# Irrigatron.net
KiCad netlist of a schematic drawn in EasyEDA
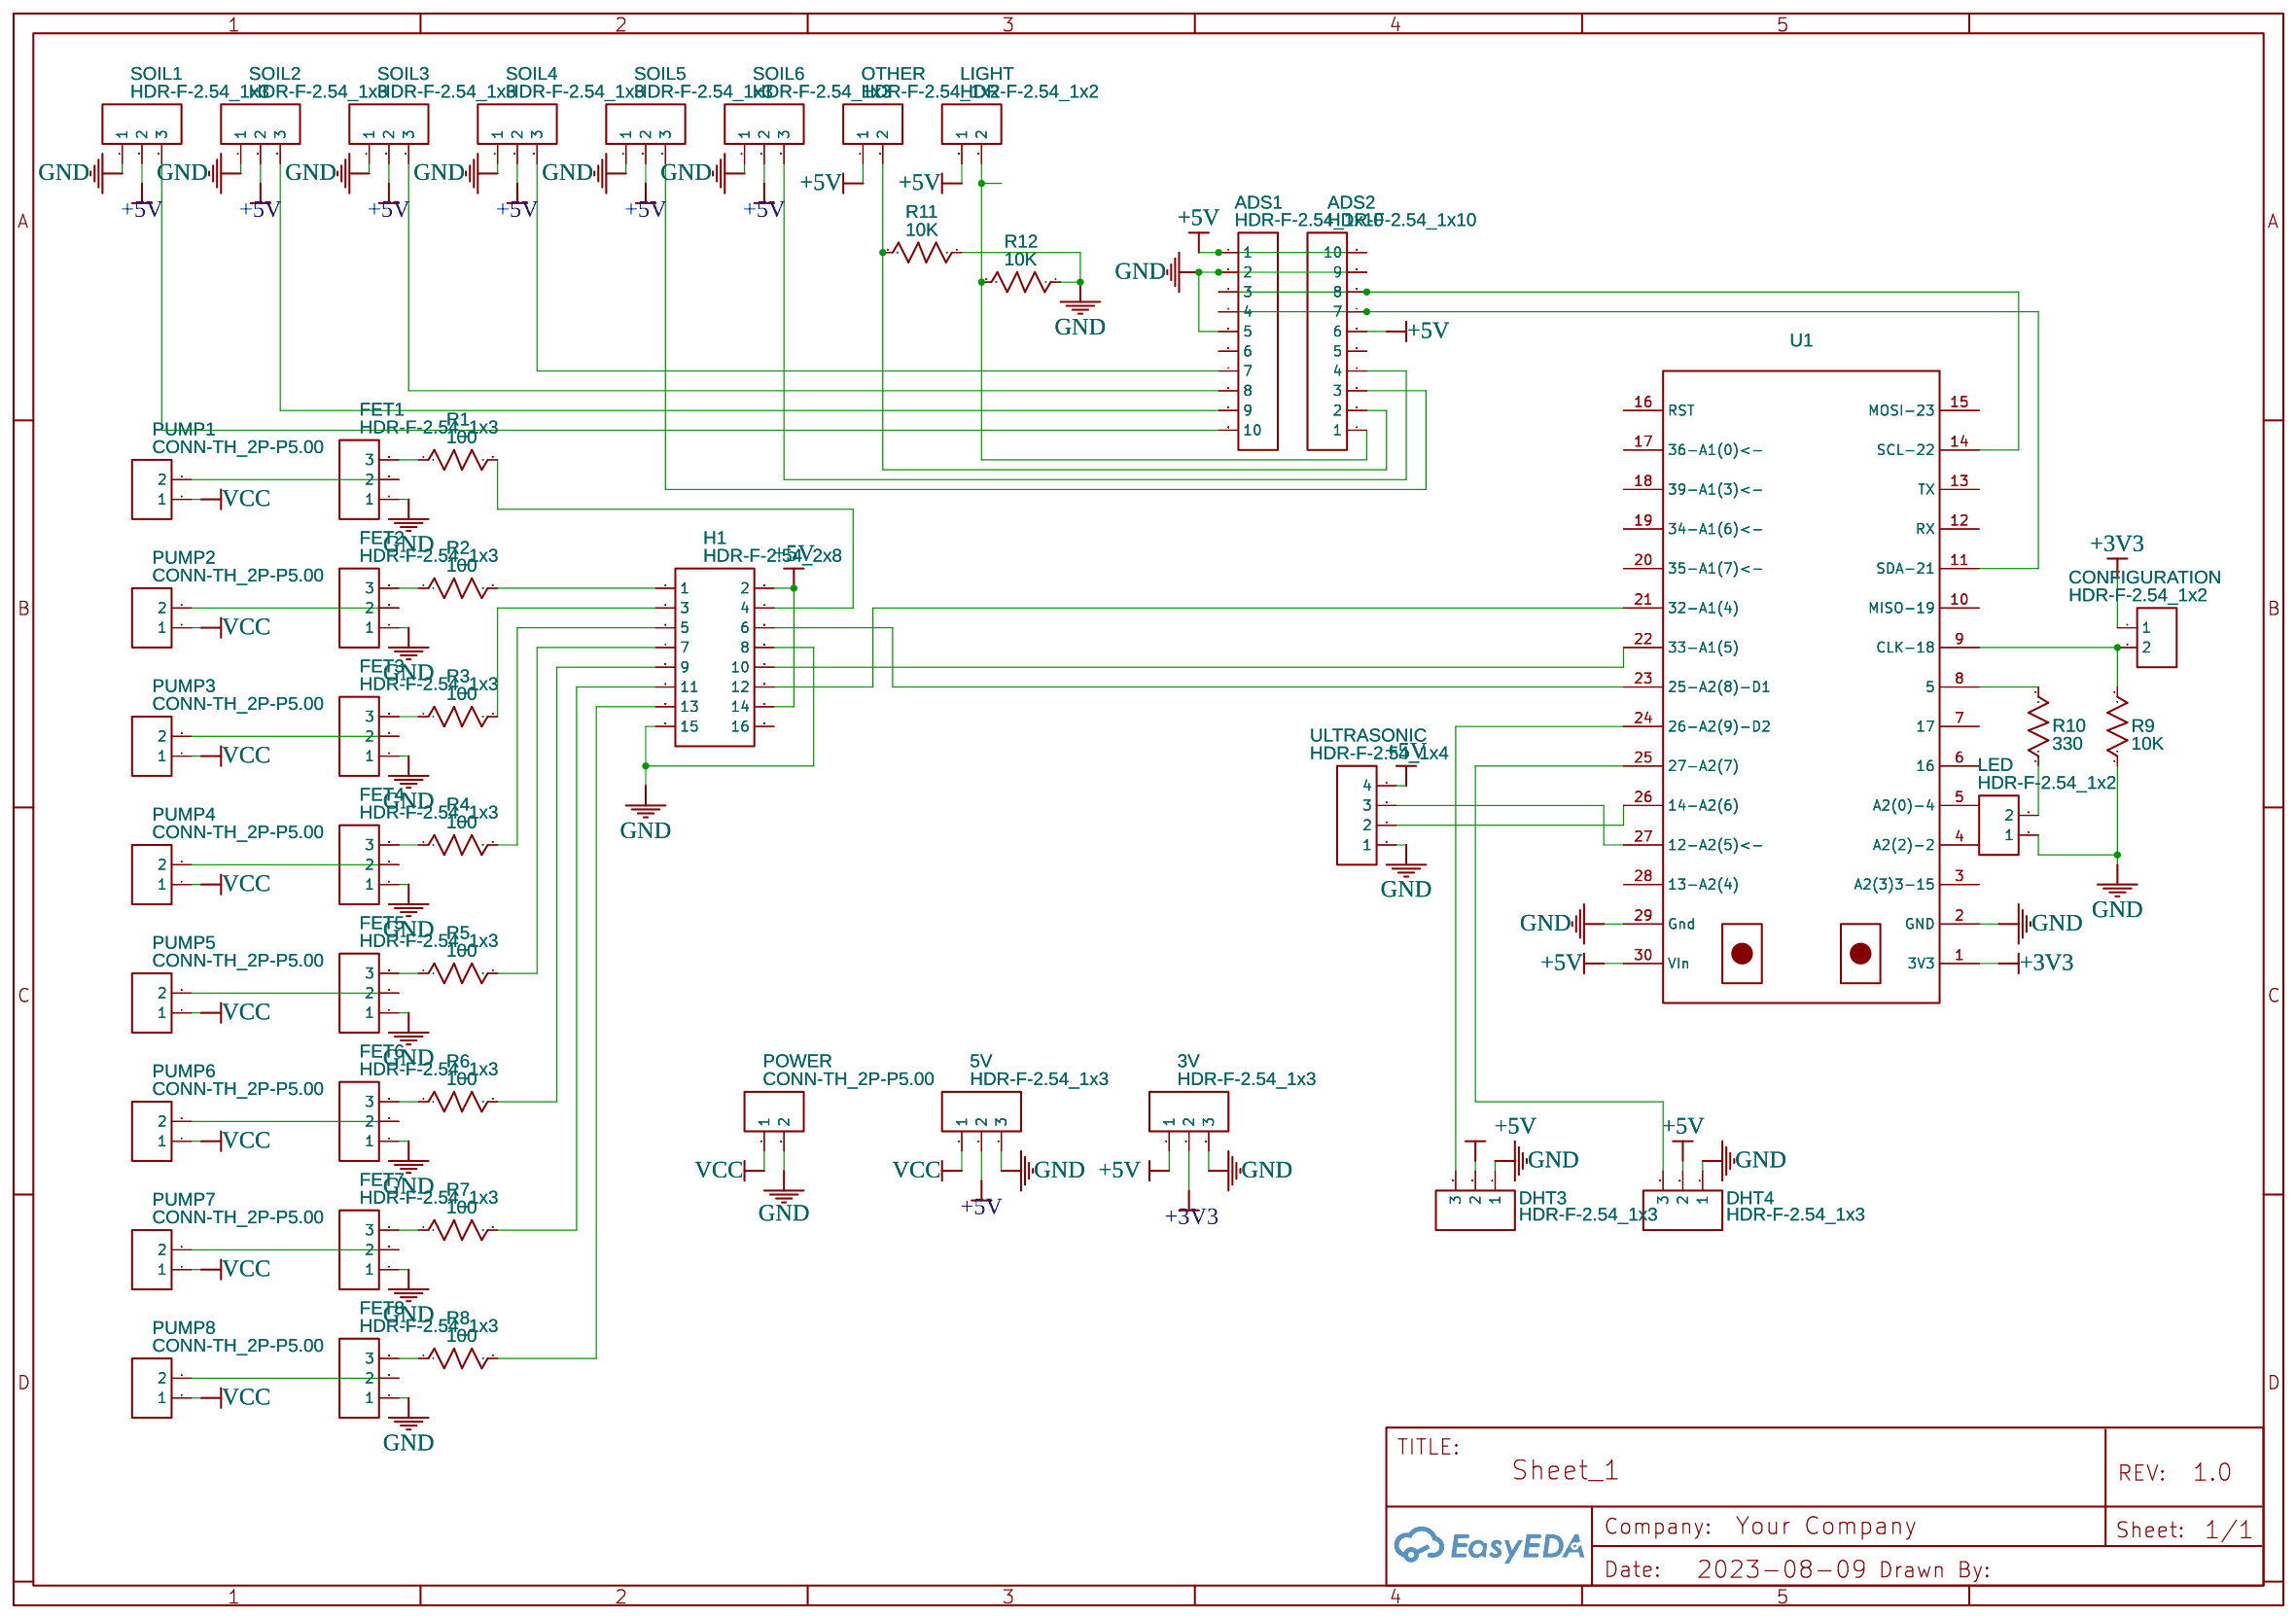
[diagram p0: schematic sheet]

(export (version "E")
  (design (tool "Eeschema 10.0.6"))
  (components
    (comp (ref "3V") (value "HDR-F-2.54_1x3") (libsource (lib "") (part "HDR-F-2.54_1x3_1")))
    (comp (ref "5V") (value "HDR-F-2.54_1x3") (libsource (lib "") (part "HDR-F-2.54_1x3")))
    (comp (ref "ADS1") (value "HDR-F-2.54_1x10") (libsource (lib "") (part "HDR-F-2.54_1x10_1")))
    (comp (ref "ADS2") (value "HDR-F-2.54_1x10") (libsource (lib "") (part "HDR-F-2.54_1x10")))
    (comp (ref "CONFIGURATION") (value "HDR-F-2.54_1x2") (libsource (lib "") (part "HDR-F-2.54_1x2_1")))
    (comp (ref "DHT3") (value "HDR-F-2.54_1x3") (libsource (lib "") (part "HDR-F-2.54_1x3_4")))
    (comp (ref "DHT4") (value "HDR-F-2.54_1x3") (libsource (lib "") (part "HDR-F-2.54_1x3_4")))
    (comp (ref "FET1") (value "HDR-F-2.54_1x3") (libsource (lib "") (part "HDR-F-2.54_1x3_3")))
    (comp (ref "FET2") (value "HDR-F-2.54_1x3") (libsource (lib "") (part "HDR-F-2.54_1x3_3")))
    (comp (ref "FET3") (value "HDR-F-2.54_1x3") (libsource (lib "") (part "HDR-F-2.54_1x3_3")))
    (comp (ref "FET4") (value "HDR-F-2.54_1x3") (libsource (lib "") (part "HDR-F-2.54_1x3_3")))
    (comp (ref "FET5") (value "HDR-F-2.54_1x3") (libsource (lib "") (part "HDR-F-2.54_1x3_3")))
    (comp (ref "FET6") (value "HDR-F-2.54_1x3") (libsource (lib "") (part "HDR-F-2.54_1x3_3")))
    (comp (ref "FET7") (value "HDR-F-2.54_1x3") (libsource (lib "") (part "HDR-F-2.54_1x3_3")))
    (comp (ref "FET8") (value "HDR-F-2.54_1x3") (libsource (lib "") (part "HDR-F-2.54_1x3_3")))
    (comp (ref "H1") (value "HDR-F-2.54_2x8") (libsource (lib "") (part "HDR-F-2.54_2x8")))
    (comp (ref "LED") (value "HDR-F-2.54_1x2") (libsource (lib "") (part "HDR-F-2.54_1x2_3")))
    (comp (ref "LIGHT") (value "HDR-F-2.54_1x2") (libsource (lib "") (part "HDR-F-2.54_1x2_2")))
    (comp (ref "OTHER") (value "HDR-F-2.54_1x2") (libsource (lib "") (part "HDR-F-2.54_1x2")))
    (comp (ref "POWER") (value "CONN-TH_2P-P5.00") (libsource (lib "") (part "CONN-TH_2P-P5.00_1")))
    (comp (ref "PUMP1") (value "CONN-TH_2P-P5.00") (libsource (lib "") (part "CONN-TH_2P-P5.00")))
    (comp (ref "PUMP2") (value "CONN-TH_2P-P5.00") (libsource (lib "") (part "CONN-TH_2P-P5.00")))
    (comp (ref "PUMP3") (value "CONN-TH_2P-P5.00") (libsource (lib "") (part "CONN-TH_2P-P5.00")))
    (comp (ref "PUMP4") (value "CONN-TH_2P-P5.00") (libsource (lib "") (part "CONN-TH_2P-P5.00")))
    (comp (ref "PUMP5") (value "CONN-TH_2P-P5.00") (libsource (lib "") (part "CONN-TH_2P-P5.00")))
    (comp (ref "PUMP6") (value "CONN-TH_2P-P5.00") (libsource (lib "") (part "CONN-TH_2P-P5.00")))
    (comp (ref "PUMP7") (value "CONN-TH_2P-P5.00") (libsource (lib "") (part "CONN-TH_2P-P5.00")))
    (comp (ref "PUMP8") (value "CONN-TH_2P-P5.00") (libsource (lib "") (part "CONN-TH_2P-P5.00")))
    (comp (ref "R1") (value "100") (libsource (lib "") (part "R_0603_US")))
    (comp (ref "R2") (value "100") (libsource (lib "") (part "R_0603_US")))
    (comp (ref "R3") (value "100") (libsource (lib "") (part "R_0603_US")))
    (comp (ref "R4") (value "100") (libsource (lib "") (part "R_0603_US")))
    (comp (ref "R5") (value "100") (libsource (lib "") (part "R_0603_US")))
    (comp (ref "R6") (value "100") (libsource (lib "") (part "R_0603_US")))
    (comp (ref "R7") (value "100") (libsource (lib "") (part "R_0603_US")))
    (comp (ref "R8") (value "100") (libsource (lib "") (part "R_0603_US")))
    (comp (ref "R9") (value "10K") (libsource (lib "") (part "R_0603_US_2")))
    (comp (ref "R10") (value "330") (libsource (lib "") (part "R_0603_US_2")))
    (comp (ref "R11") (value "10K") (libsource (lib "") (part "R_0603_US_1")))
    (comp (ref "R12") (value "10K") (libsource (lib "") (part "R_0603_US_1")))
    (comp (ref "SOIL1") (value "HDR-F-2.54_1x3") (libsource (lib "") (part "HDR-F-2.54_1x3_2")))
    (comp (ref "SOIL2") (value "HDR-F-2.54_1x3") (libsource (lib "") (part "HDR-F-2.54_1x3_2")))
    (comp (ref "SOIL3") (value "HDR-F-2.54_1x3") (libsource (lib "") (part "HDR-F-2.54_1x3_2")))
    (comp (ref "SOIL4") (value "HDR-F-2.54_1x3") (libsource (lib "") (part "HDR-F-2.54_1x3_2")))
    (comp (ref "SOIL5") (value "HDR-F-2.54_1x3") (libsource (lib "") (part "HDR-F-2.54_1x3_2")))
    (comp (ref "SOIL6") (value "HDR-F-2.54_1x3") (libsource (lib "") (part "HDR-F-2.54_1x3_2")))
    (comp (ref "U1") (value "NO") (libsource (lib "") (part "DOIT ESP32 DEVKIT V1 (30pins)")))
    (comp (ref "ULTRASONIC") (value "HDR-F-2.54_1x4") (libsource (lib "") (part "HDR-F-2.54_1x4")))
  )
  (nets
    (net (code "1") (name "+3V3") (class "Default")
      (node (ref "3V") (pin "2") (pinfunction "2_2") (pintype "input"))
      (node (ref "CONFIGURATION") (pin "1") (pinfunction "1_1") (pintype "input"))
      (node (ref "U1") (pin "1") (pinfunction "3V3_1") (pintype "unspecified"))
    )
    (net (code "2") (name "+5V") (class "Default")
      (node (ref "3V") (pin "1") (pinfunction "1_1") (pintype "input"))
      (node (ref "5V") (pin "2") (pinfunction "2_2") (pintype "input"))
      (node (ref "ADS1") (pin "1") (pinfunction "1_1") (pintype "unspecified"))
      (node (ref "ADS2") (pin "10") (pinfunction "10_10") (pintype "unspecified"))
      (node (ref "ADS2") (pin "6") (pinfunction "6_6") (pintype "unspecified"))
      (node (ref "DHT3") (pin "2") (pinfunction "2_2") (pintype "input"))
      (node (ref "DHT4") (pin "2") (pinfunction "2_2") (pintype "input"))
      (node (ref "H1") (pin "14") (pinfunction "14_14") (pintype "input"))
      (node (ref "H1") (pin "2") (pinfunction "2_2") (pintype "input"))
      (node (ref "LIGHT") (pin "1") (pinfunction "1_1") (pintype "input"))
      (node (ref "OTHER") (pin "1") (pinfunction "1_1") (pintype "input"))
      (node (ref "SOIL1") (pin "2") (pinfunction "2_2") (pintype "input"))
      (node (ref "SOIL2") (pin "2") (pinfunction "2_2") (pintype "input"))
      (node (ref "SOIL3") (pin "2") (pinfunction "2_2") (pintype "input"))
      (node (ref "SOIL4") (pin "2") (pinfunction "2_2") (pintype "input"))
      (node (ref "SOIL5") (pin "2") (pinfunction "2_2") (pintype "input"))
      (node (ref "SOIL6") (pin "2") (pinfunction "2_2") (pintype "input"))
      (node (ref "U1") (pin "30") (pinfunction "VIn_30") (pintype "unspecified"))
      (node (ref "ULTRASONIC") (pin "4") (pinfunction "4_4") (pintype "unspecified"))
    )
    (net (code "3") (name "GND") (class "Default")
      (node (ref "3V") (pin "3") (pinfunction "3_3") (pintype "input"))
      (node (ref "5V") (pin "3") (pinfunction "3_3") (pintype "input"))
      (node (ref "ADS1") (pin "2") (pinfunction "2_2") (pintype "unspecified"))
      (node (ref "ADS1") (pin "5") (pinfunction "5_5") (pintype "unspecified"))
      (node (ref "ADS2") (pin "9") (pinfunction "9_9") (pintype "unspecified"))
      (node (ref "DHT3") (pin "1") (pinfunction "1_1") (pintype "input"))
      (node (ref "DHT4") (pin "1") (pinfunction "1_1") (pintype "input"))
      (node (ref "FET1") (pin "1") (pinfunction "1_1") (pintype "input"))
      (node (ref "FET2") (pin "1") (pinfunction "1_1") (pintype "input"))
      (node (ref "FET3") (pin "1") (pinfunction "1_1") (pintype "input"))
      (node (ref "FET4") (pin "1") (pinfunction "1_1") (pintype "input"))
      (node (ref "FET5") (pin "1") (pinfunction "1_1") (pintype "input"))
      (node (ref "FET6") (pin "1") (pinfunction "1_1") (pintype "input"))
      (node (ref "FET7") (pin "1") (pinfunction "1_1") (pintype "input"))
      (node (ref "FET8") (pin "1") (pinfunction "1_1") (pintype "input"))
      (node (ref "H1") (pin "15") (pinfunction "15_15") (pintype "input"))
      (node (ref "H1") (pin "8") (pinfunction "8_8") (pintype "input"))
      (node (ref "LED") (pin "1") (pinfunction "1_1") (pintype "input"))
      (node (ref "POWER") (pin "2") (pinfunction "2_2") (pintype "unspecified"))
      (node (ref "R11") (pin "1") (pinfunction "1_1") (pintype "unspecified"))
      (node (ref "R12") (pin "1") (pinfunction "1_1") (pintype "unspecified"))
      (node (ref "R9") (pin "1") (pinfunction "1_1") (pintype "unspecified"))
      (node (ref "SOIL1") (pin "1") (pinfunction "1_1") (pintype "input"))
      (node (ref "SOIL2") (pin "1") (pinfunction "1_1") (pintype "input"))
      (node (ref "SOIL3") (pin "1") (pinfunction "1_1") (pintype "input"))
      (node (ref "SOIL4") (pin "1") (pinfunction "1_1") (pintype "input"))
      (node (ref "SOIL5") (pin "1") (pinfunction "1_1") (pintype "input"))
      (node (ref "SOIL6") (pin "1") (pinfunction "1_1") (pintype "input"))
      (node (ref "U1") (pin "2") (pinfunction "GND_2") (pintype "unspecified"))
      (node (ref "U1") (pin "29") (pinfunction "Gnd_29") (pintype "unspecified"))
      (node (ref "ULTRASONIC") (pin "1") (pinfunction "1_1") (pintype "unspecified"))
    )
    (net (code "4") (name "Net-(ADS1-Pad7)") (class "Default")
      (node (ref "ADS1") (pin "7") (pinfunction "7_7") (pintype "unspecified"))
      (node (ref "SOIL4") (pin "3") (pinfunction "3_3") (pintype "input"))
    )
    (net (code "5") (name "Net-(ADS1-Pad8)") (class "Default")
      (node (ref "ADS1") (pin "8") (pinfunction "8_8") (pintype "unspecified"))
      (node (ref "SOIL3") (pin "3") (pinfunction "3_3") (pintype "input"))
    )
    (net (code "6") (name "Net-(ADS1-Pad9)") (class "Default")
      (node (ref "ADS1") (pin "9") (pinfunction "9_9") (pintype "unspecified"))
      (node (ref "SOIL2") (pin "3") (pinfunction "3_3") (pintype "input"))
    )
    (net (code "7") (name "Net-(ADS1-Pad10)") (class "Default")
      (node (ref "ADS1") (pin "10") (pinfunction "10_10") (pintype "unspecified"))
      (node (ref "SOIL1") (pin "3") (pinfunction "3_3") (pintype "input"))
    )
    (net (code "8") (name "Net-(ADS2-Pad1)") (class "Default")
      (node (ref "ADS2") (pin "1") (pinfunction "1_1") (pintype "unspecified"))
      (node (ref "LIGHT") (pin "2") (pinfunction "2_2") (pintype "input"))
      (node (ref "R12") (pin "2") (pinfunction "2_2") (pintype "unspecified"))
    )
    (net (code "9") (name "Net-(ADS2-Pad2)") (class "Default")
      (node (ref "ADS2") (pin "2") (pinfunction "2_2") (pintype "unspecified"))
      (node (ref "OTHER") (pin "2") (pinfunction "2_2") (pintype "input"))
      (node (ref "R11") (pin "2") (pinfunction "2_2") (pintype "unspecified"))
    )
    (net (code "10") (name "Net-(ADS2-Pad3)") (class "Default")
      (node (ref "ADS2") (pin "3") (pinfunction "3_3") (pintype "unspecified"))
      (node (ref "SOIL5") (pin "3") (pinfunction "3_3") (pintype "input"))
    )
    (net (code "11") (name "Net-(ADS2-Pad4)") (class "Default")
      (node (ref "ADS2") (pin "4") (pinfunction "4_4") (pintype "unspecified"))
      (node (ref "SOIL6") (pin "3") (pinfunction "3_3") (pintype "input"))
    )
    (net (code "12") (name "Net-(FET1-Pad2)") (class "Default")
      (node (ref "FET1") (pin "2") (pinfunction "2_2") (pintype "input"))
      (node (ref "PUMP1") (pin "2") (pinfunction "2_2") (pintype "unspecified"))
    )
    (net (code "13") (name "Net-(FET1-Pad3)") (class "Default")
      (node (ref "FET1") (pin "3") (pinfunction "3_3") (pintype "input"))
      (node (ref "R1") (pin "1") (pinfunction "1_1") (pintype "unspecified"))
    )
    (net (code "14") (name "Net-(FET2-Pad2)") (class "Default")
      (node (ref "FET2") (pin "2") (pinfunction "2_2") (pintype "input"))
      (node (ref "PUMP2") (pin "2") (pinfunction "2_2") (pintype "unspecified"))
    )
    (net (code "15") (name "Net-(FET2-Pad3)") (class "Default")
      (node (ref "FET2") (pin "3") (pinfunction "3_3") (pintype "input"))
      (node (ref "R2") (pin "1") (pinfunction "1_1") (pintype "unspecified"))
    )
    (net (code "16") (name "Net-(FET3-Pad2)") (class "Default")
      (node (ref "FET3") (pin "2") (pinfunction "2_2") (pintype "input"))
      (node (ref "PUMP3") (pin "2") (pinfunction "2_2") (pintype "unspecified"))
    )
    (net (code "17") (name "Net-(FET3-Pad3)") (class "Default")
      (node (ref "FET3") (pin "3") (pinfunction "3_3") (pintype "input"))
      (node (ref "R3") (pin "1") (pinfunction "1_1") (pintype "unspecified"))
    )
    (net (code "18") (name "Net-(FET4-Pad2)") (class "Default")
      (node (ref "FET4") (pin "2") (pinfunction "2_2") (pintype "input"))
      (node (ref "PUMP4") (pin "2") (pinfunction "2_2") (pintype "unspecified"))
    )
    (net (code "19") (name "Net-(FET4-Pad3)") (class "Default")
      (node (ref "FET4") (pin "3") (pinfunction "3_3") (pintype "input"))
      (node (ref "R4") (pin "1") (pinfunction "1_1") (pintype "unspecified"))
    )
    (net (code "20") (name "Net-(FET5-Pad2)") (class "Default")
      (node (ref "FET5") (pin "2") (pinfunction "2_2") (pintype "input"))
      (node (ref "PUMP5") (pin "2") (pinfunction "2_2") (pintype "unspecified"))
    )
    (net (code "21") (name "Net-(FET5-Pad3)") (class "Default")
      (node (ref "FET5") (pin "3") (pinfunction "3_3") (pintype "input"))
      (node (ref "R5") (pin "1") (pinfunction "1_1") (pintype "unspecified"))
    )
    (net (code "22") (name "Net-(FET6-Pad2)") (class "Default")
      (node (ref "FET6") (pin "2") (pinfunction "2_2") (pintype "input"))
      (node (ref "PUMP6") (pin "2") (pinfunction "2_2") (pintype "unspecified"))
    )
    (net (code "23") (name "Net-(FET6-Pad3)") (class "Default")
      (node (ref "FET6") (pin "3") (pinfunction "3_3") (pintype "input"))
      (node (ref "R6") (pin "1") (pinfunction "1_1") (pintype "unspecified"))
    )
    (net (code "24") (name "Net-(FET7-Pad2)") (class "Default")
      (node (ref "FET7") (pin "2") (pinfunction "2_2") (pintype "input"))
      (node (ref "PUMP7") (pin "2") (pinfunction "2_2") (pintype "unspecified"))
    )
    (net (code "25") (name "Net-(FET7-Pad3)") (class "Default")
      (node (ref "FET7") (pin "3") (pinfunction "3_3") (pintype "input"))
      (node (ref "R7") (pin "1") (pinfunction "1_1") (pintype "unspecified"))
    )
    (net (code "26") (name "Net-(FET8-Pad2)") (class "Default")
      (node (ref "FET8") (pin "2") (pinfunction "2_2") (pintype "input"))
      (node (ref "PUMP8") (pin "2") (pinfunction "2_2") (pintype "unspecified"))
    )
    (net (code "27") (name "Net-(FET8-Pad3)") (class "Default")
      (node (ref "FET8") (pin "3") (pinfunction "3_3") (pintype "input"))
      (node (ref "R8") (pin "1") (pinfunction "1_1") (pintype "unspecified"))
    )
    (net (code "28") (name "Net-(H1-Pad1)") (class "Default")
      (node (ref "H1") (pin "1") (pinfunction "1_1") (pintype "input"))
      (node (ref "R2") (pin "2") (pinfunction "2_2") (pintype "unspecified"))
    )
    (net (code "29") (name "Net-(H1-Pad3)") (class "Default")
      (node (ref "H1") (pin "3") (pinfunction "3_3") (pintype "input"))
      (node (ref "R3") (pin "2") (pinfunction "2_2") (pintype "unspecified"))
    )
    (net (code "30") (name "Net-(H1-Pad4)") (class "Default")
      (node (ref "H1") (pin "4") (pinfunction "4_4") (pintype "input"))
      (node (ref "R1") (pin "2") (pinfunction "2_2") (pintype "unspecified"))
    )
    (net (code "31") (name "Net-(H1-Pad5)") (class "Default")
      (node (ref "H1") (pin "5") (pinfunction "5_5") (pintype "input"))
      (node (ref "R4") (pin "2") (pinfunction "2_2") (pintype "unspecified"))
    )
    (net (code "32") (name "Net-(H1-Pad7)") (class "Default")
      (node (ref "H1") (pin "7") (pinfunction "7_7") (pintype "input"))
      (node (ref "R5") (pin "2") (pinfunction "2_2") (pintype "unspecified"))
    )
    (net (code "33") (name "Net-(H1-Pad9)") (class "Default")
      (node (ref "H1") (pin "9") (pinfunction "9_9") (pintype "input"))
      (node (ref "R6") (pin "2") (pinfunction "2_2") (pintype "unspecified"))
    )
    (net (code "34") (name "Net-(H1-Pad11)") (class "Default")
      (node (ref "H1") (pin "11") (pinfunction "11_11") (pintype "input"))
      (node (ref "R7") (pin "2") (pinfunction "2_2") (pintype "unspecified"))
    )
    (net (code "35") (name "Net-(H1-Pad13)") (class "Default")
      (node (ref "H1") (pin "13") (pinfunction "13_13") (pintype "input"))
      (node (ref "R8") (pin "2") (pinfunction "2_2") (pintype "unspecified"))
    )
    (net (code "36") (name "Net-(LED-Pad2)") (class "Default")
      (node (ref "LED") (pin "2") (pinfunction "2_2") (pintype "input"))
      (node (ref "R10") (pin "1") (pinfunction "1_1") (pintype "unspecified"))
    )
    (net (code "37") (name "Net-(U1-5)") (class "Default")
      (node (ref "R10") (pin "2") (pinfunction "2_2") (pintype "unspecified"))
      (node (ref "U1") (pin "8") (pinfunction "5_8") (pintype "unspecified"))
    )
    (net (code "38") (name "Net-(U1-12-A2(5)<-)") (class "Default")
      (node (ref "U1") (pin "27") (pinfunction "12-A2(5)<-_27") (pintype "unspecified"))
      (node (ref "ULTRASONIC") (pin "3") (pinfunction "3_3") (pintype "unspecified"))
    )
    (net (code "39") (name "Net-(U1-14-A2(6))") (class "Default")
      (node (ref "U1") (pin "26") (pinfunction "14-A2(6)_26") (pintype "unspecified"))
      (node (ref "ULTRASONIC") (pin "2") (pinfunction "2_2") (pintype "unspecified"))
    )
    (net (code "40") (name "Net-(U1-25-A2(8)-D1)") (class "Default")
      (node (ref "H1") (pin "6") (pinfunction "6_6") (pintype "input"))
      (node (ref "U1") (pin "23") (pinfunction "25-A2(8)-D1_23") (pintype "unspecified"))
    )
    (net (code "41") (name "Net-(U1-26-A2(9)-D2)") (class "Default")
      (node (ref "DHT3") (pin "3") (pinfunction "3_3") (pintype "input"))
      (node (ref "U1") (pin "24") (pinfunction "26-A2(9)-D2_24") (pintype "unspecified"))
    )
    (net (code "42") (name "Net-(U1-27-A2(7))") (class "Default")
      (node (ref "DHT4") (pin "3") (pinfunction "3_3") (pintype "input"))
      (node (ref "U1") (pin "25") (pinfunction "27-A2(7)_25") (pintype "unspecified"))
    )
    (net (code "43") (name "Net-(U1-32-A1(4))") (class "Default")
      (node (ref "H1") (pin "12") (pinfunction "12_12") (pintype "input"))
      (node (ref "U1") (pin "21") (pinfunction "32-A1(4)_21") (pintype "unspecified"))
    )
    (net (code "44") (name "Net-(U1-33-A1(5))") (class "Default")
      (node (ref "H1") (pin "10") (pinfunction "10_10") (pintype "input"))
      (node (ref "U1") (pin "22") (pinfunction "33-A1(5)_22") (pintype "unspecified"))
    )
    (net (code "45") (name "Net-(U1-CLK-18)") (class "Default")
      (node (ref "CONFIGURATION") (pin "2") (pinfunction "2_2") (pintype "input"))
      (node (ref "R9") (pin "2") (pinfunction "2_2") (pintype "unspecified"))
      (node (ref "U1") (pin "9") (pinfunction "CLK-18_9") (pintype "unspecified"))
    )
    (net (code "46") (name "Net-(U1-SCL-22)") (class "Default")
      (node (ref "ADS1") (pin "3") (pinfunction "3_3") (pintype "unspecified"))
      (node (ref "ADS2") (pin "8") (pinfunction "8_8") (pintype "unspecified"))
      (node (ref "U1") (pin "14") (pinfunction "SCL-22_14") (pintype "unspecified"))
    )
    (net (code "47") (name "Net-(U1-SDA-21)") (class "Default")
      (node (ref "ADS1") (pin "4") (pinfunction "4_4") (pintype "unspecified"))
      (node (ref "ADS2") (pin "7") (pinfunction "7_7") (pintype "unspecified"))
      (node (ref "U1") (pin "11") (pinfunction "SDA-21_11") (pintype "unspecified"))
    )
    (net (code "48") (name "VCC") (class "Default")
      (node (ref "5V") (pin "1") (pinfunction "1_1") (pintype "input"))
      (node (ref "POWER") (pin "1") (pinfunction "1_1") (pintype "unspecified"))
      (node (ref "PUMP1") (pin "1") (pinfunction "1_1") (pintype "unspecified"))
      (node (ref "PUMP2") (pin "1") (pinfunction "1_1") (pintype "unspecified"))
      (node (ref "PUMP3") (pin "1") (pinfunction "1_1") (pintype "unspecified"))
      (node (ref "PUMP4") (pin "1") (pinfunction "1_1") (pintype "unspecified"))
      (node (ref "PUMP5") (pin "1") (pinfunction "1_1") (pintype "unspecified"))
      (node (ref "PUMP6") (pin "1") (pinfunction "1_1") (pintype "unspecified"))
      (node (ref "PUMP7") (pin "1") (pinfunction "1_1") (pintype "unspecified"))
      (node (ref "PUMP8") (pin "1") (pinfunction "1_1") (pintype "unspecified"))
    )
    (net (code "49") (name "unconnected-(ADS1-Pad6)") (class "Default")
      (node (ref "ADS1") (pin "6") (pinfunction "6_6") (pintype "unspecified"))
    )
    (net (code "50") (name "unconnected-(ADS2-Pad5)") (class "Default")
      (node (ref "ADS2") (pin "5") (pinfunction "5_5") (pintype "unspecified"))
    )
    (net (code "51") (name "unconnected-(H1-Pad16)") (class "Default")
      (node (ref "H1") (pin "16") (pinfunction "16_16") (pintype "input"))
    )
    (net (code "52") (name "unconnected-(U1-13-A2(4)-Pad28)") (class "Default")
      (node (ref "U1") (pin "28") (pinfunction "13-A2(4)_28") (pintype "unspecified"))
    )
    (net (code "53") (name "unconnected-(U1-16-Pad6)") (class "Default")
      (node (ref "U1") (pin "6") (pinfunction "16_6") (pintype "unspecified"))
    )
    (net (code "54") (name "unconnected-(U1-17-Pad7)") (class "Default")
      (node (ref "U1") (pin "7") (pinfunction "17_7") (pintype "unspecified"))
    )
    (net (code "55") (name "unconnected-(U1-34-A1(6)<--Pad19)") (class "Default")
      (node (ref "U1") (pin "19") (pinfunction "34-A1(6)<-_19") (pintype "unspecified"))
    )
    (net (code "56") (name "unconnected-(U1-35-A1(7)<--Pad20)") (class "Default")
      (node (ref "U1") (pin "20") (pinfunction "35-A1(7)<-_20") (pintype "unspecified"))
    )
    (net (code "57") (name "unconnected-(U1-36-A1(0)<--Pad17)") (class "Default")
      (node (ref "U1") (pin "17") (pinfunction "36-A1(0)<-_17") (pintype "unspecified"))
    )
    (net (code "58") (name "unconnected-(U1-39-A1(3)<--Pad18)") (class "Default")
      (node (ref "U1") (pin "18") (pinfunction "39-A1(3)<-_18") (pintype "unspecified"))
    )
    (net (code "59") (name "unconnected-(U1-A2(0)-4-Pad5)") (class "Default")
      (node (ref "U1") (pin "5") (pinfunction "A2(0)-4_5") (pintype "unspecified"))
    )
    (net (code "60") (name "unconnected-(U1-A2(2)-2-Pad4)") (class "Default")
      (node (ref "U1") (pin "4") (pinfunction "A2(2)-2_4") (pintype "unspecified"))
    )
    (net (code "61") (name "unconnected-(U1-A2(3)3-15-Pad3)") (class "Default")
      (node (ref "U1") (pin "3") (pinfunction "A2(3)3-15_3") (pintype "unspecified"))
    )
    (net (code "62") (name "unconnected-(U1-MISO-19-Pad10)") (class "Default")
      (node (ref "U1") (pin "10") (pinfunction "MISO-19_10") (pintype "unspecified"))
    )
    (net (code "63") (name "unconnected-(U1-MOSI-23-Pad15)") (class "Default")
      (node (ref "U1") (pin "15") (pinfunction "MOSI-23_15") (pintype "unspecified"))
    )
    (net (code "64") (name "unconnected-(U1-RST-Pad16)") (class "Default")
      (node (ref "U1") (pin "16") (pinfunction "RST_16") (pintype "unspecified"))
    )
    (net (code "65") (name "unconnected-(U1-RX-Pad12)") (class "Default")
      (node (ref "U1") (pin "12") (pinfunction "RX_12") (pintype "unspecified"))
    )
    (net (code "66") (name "unconnected-(U1-TX-Pad13)") (class "Default")
      (node (ref "U1") (pin "13") (pinfunction "TX_13") (pintype "unspecified"))
    )
  )
)
